# Powerlolu_Pololu.net
KiCad netlist of a schematic drawn in EAGLE
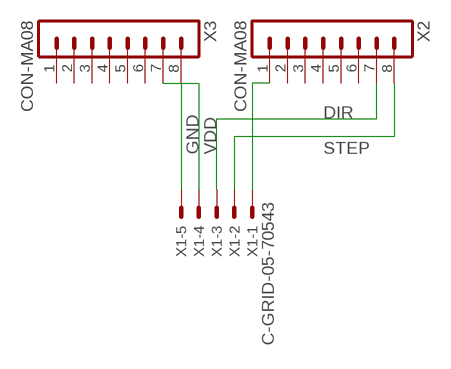
[diagram p0: schematic, sheet 1]

(export (version "E")
  (design (tool "Eeschema 10.0.6"))
  (components
    (comp (ref "X1")
      (value "C-GRID-05-70543")
      (footprint "eagle-import:70543-05")
      (libsource (lib "eagle-import") (part "C-GRID-05-70543"))
    )
    (comp (ref "X2")
      (value "CON-MA08")
      (footprint "eagle-import:MA08")
      (libsource (lib "eagle-import") (part "CON-MA08"))
    )
    (comp (ref "X3")
      (value "CON-MA08")
      (footprint "eagle-import:MA08")
      (libsource (lib "eagle-import") (part "CON-MA08"))
    )
  )
  (nets
    (net (code "1") (name "/DIR") (class "Default")
      (node (ref "X1") (pin "3") (pinfunction "S_3") (pintype "passive"))
      (node (ref "X2") (pin "7") (pinfunction "7_7") (pintype "passive"))
    )
    (net (code "2") (name "/GND") (class "Default")
      (node (ref "X1") (pin "5") (pinfunction "S_5") (pintype "passive"))
      (node (ref "X3") (pin "8") (pinfunction "8_8") (pintype "passive"))
    )
    (net (code "3") (name "/STEP") (class "Default")
      (node (ref "X1") (pin "2") (pinfunction "S_2") (pintype "passive"))
      (node (ref "X2") (pin "8") (pinfunction "8_8") (pintype "passive"))
    )
    (net (code "4") (name "/VDD") (class "Default")
      (node (ref "X1") (pin "4") (pinfunction "S_4") (pintype "passive"))
      (node (ref "X3") (pin "7") (pinfunction "7_7") (pintype "passive"))
    )
    (net (code "5") (name "Net-(X1A-S)") (class "Default")
      (node (ref "X1") (pin "1") (pinfunction "S_1") (pintype "passive"))
      (node (ref "X2") (pin "1") (pinfunction "1_1") (pintype "passive"))
    )
    (net (code "6") (name "unconnected-(X2-Pad2)") (class "Default")
      (node (ref "X2") (pin "2") (pinfunction "2_2") (pintype "passive"))
    )
    (net (code "7") (name "unconnected-(X2-Pad3)") (class "Default")
      (node (ref "X2") (pin "3") (pinfunction "3_3") (pintype "passive"))
    )
    (net (code "8") (name "unconnected-(X2-Pad4)") (class "Default")
      (node (ref "X2") (pin "4") (pinfunction "4_4") (pintype "passive"))
    )
    (net (code "9") (name "unconnected-(X2-Pad5)") (class "Default")
      (node (ref "X2") (pin "5") (pinfunction "5_5") (pintype "passive"))
    )
    (net (code "10") (name "unconnected-(X2-Pad6)") (class "Default")
      (node (ref "X2") (pin "6") (pinfunction "6_6") (pintype "passive"))
    )
    (net (code "11") (name "unconnected-(X3-Pad1)") (class "Default")
      (node (ref "X3") (pin "1") (pinfunction "1_1") (pintype "passive"))
    )
    (net (code "12") (name "unconnected-(X3-Pad2)") (class "Default")
      (node (ref "X3") (pin "2") (pinfunction "2_2") (pintype "passive"))
    )
    (net (code "13") (name "unconnected-(X3-Pad3)") (class "Default")
      (node (ref "X3") (pin "3") (pinfunction "3_3") (pintype "passive"))
    )
    (net (code "14") (name "unconnected-(X3-Pad4)") (class "Default")
      (node (ref "X3") (pin "4") (pinfunction "4_4") (pintype "passive"))
    )
    (net (code "15") (name "unconnected-(X3-Pad5)") (class "Default")
      (node (ref "X3") (pin "5") (pinfunction "5_5") (pintype "passive"))
    )
    (net (code "16") (name "unconnected-(X3-Pad6)") (class "Default")
      (node (ref "X3") (pin "6") (pinfunction "6_6") (pintype "passive"))
    )
  )
)
